# PP_8_14_2012.net
KiCad netlist of a schematic drawn in Altium Designer
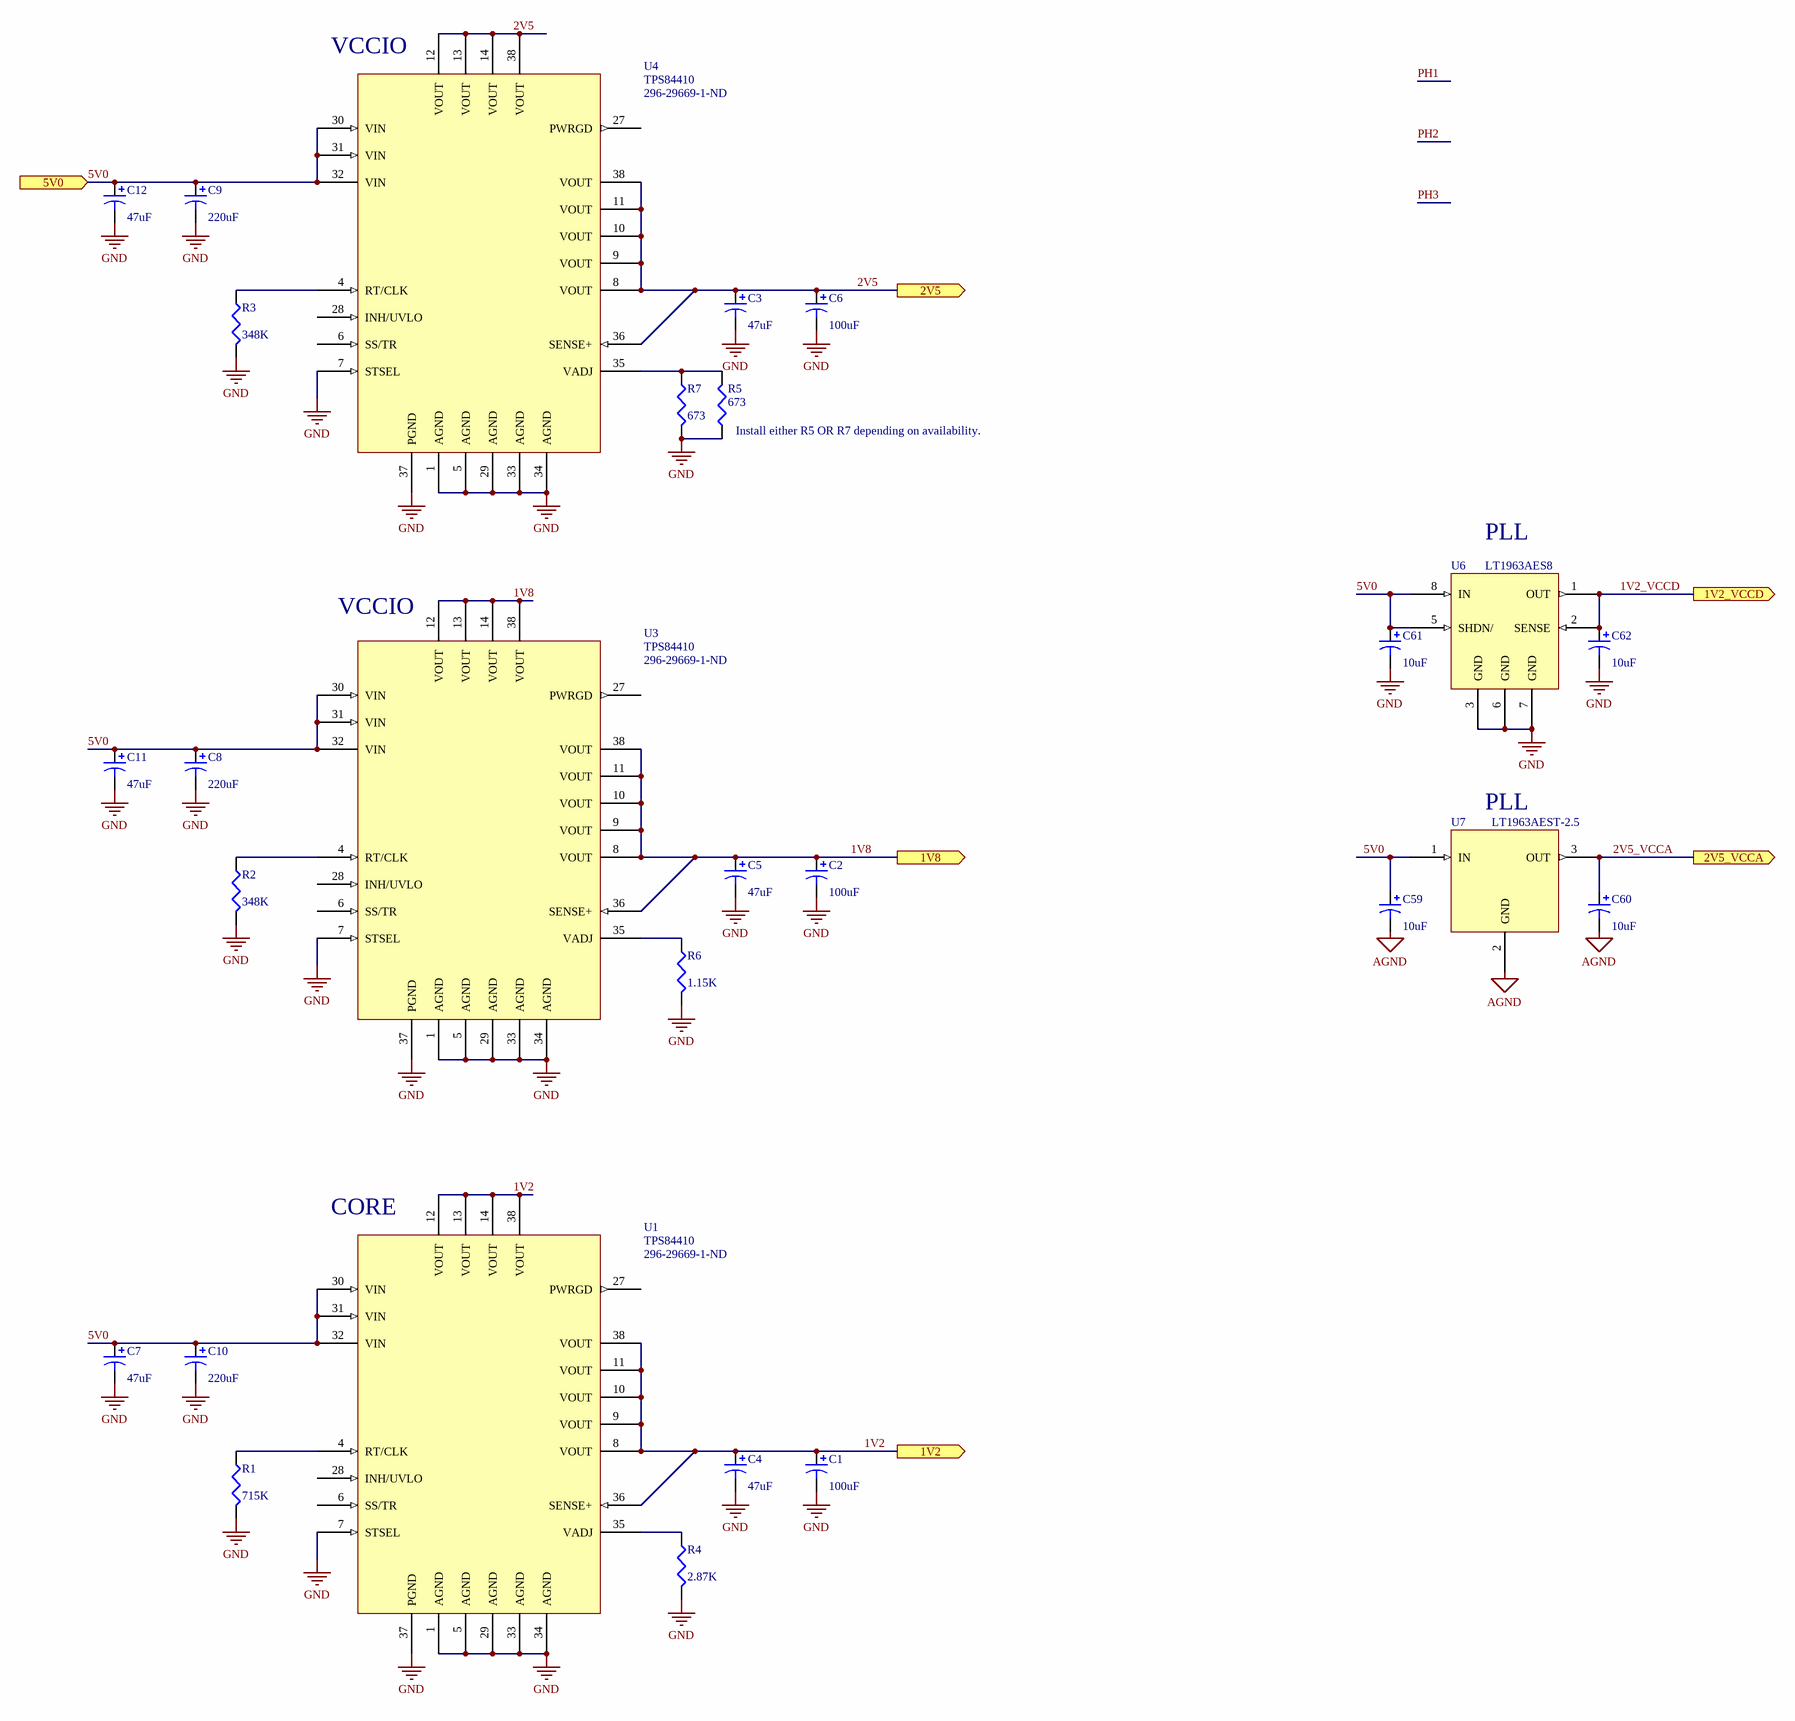
[diagram p0: PP 8_14_2012.SchDoc]

(export (version "E")
  (design (tool "Eeschema 10.0.6"))
  (components
    (comp (ref "C1")
      (value "100uF")
      (footprint "TC3528-1411")
      (description "CAP TANT 100UF 10V 20% 1210")
      (fields (field (name "Comment") "100 uF") (field (name "PUBLISHER") "Altium Limited"))
      (libsource (lib "Miscellaneous Devices") (part "Cap Pol3"))
    )
    (comp (ref "C2")
      (value "100uF")
      (footprint "TC3528-1411")
      (description "CAP TANT 100UF 10V 20% 1210")
      (fields (field (name "Comment") "100 uF") (field (name "PUBLISHER") "Altium Limited"))
      (libsource (lib "Miscellaneous Devices") (part "Cap Pol3"))
    )
    (comp (ref "C3")
      (value "47uF")
      (footprint "TC3528-1411")
      (description "CAP TANT 47UF 10V 10% 1411")
      (fields (field (name "Comment") "100 uF") (field (name "PUBLISHER") "Altium Limited"))
      (libsource (lib "Miscellaneous Devices") (part "Cap Pol3"))
    )
    (comp (ref "C4")
      (value "47uF")
      (footprint "TC3528-1411")
      (description "CAP TANT 47UF 10V 10% 1411")
      (fields (field (name "Comment") "47 uF") (field (name "PUBLISHER") "Altium Limited"))
      (libsource (lib "Miscellaneous Devices") (part "Cap Pol3"))
    )
    (comp (ref "C5")
      (value "47uF")
      (footprint "TC3528-1411")
      (description "CAP TANT 47UF 10V 10% 1411")
      (fields (field (name "Comment") "47 uF") (field (name "PUBLISHER") "Altium Limited"))
      (libsource (lib "Miscellaneous Devices") (part "Cap Pol3"))
    )
    (comp (ref "C6")
      (value "100uF")
      (footprint "TC3528-1411")
      (description "CAP TANT 100UF 10V 20% 1210")
      (fields (field (name "Comment") "47 uF") (field (name "PUBLISHER") "Altium Limited"))
      (libsource (lib "Miscellaneous Devices") (part "Cap Pol3"))
    )
    (comp (ref "C7")
      (value "47uF")
      (footprint "TC3528-1411")
      (description "CAP TANT 47UF 10V 10% 1411")
      (fields (field (name "Comment") "220uF") (field (name "PUBLISHER") "Altium Limited"))
      (libsource (lib "Miscellaneous Devices") (part "Cap Pol3"))
    )
    (comp (ref "C8")
      (value "220uF")
      (footprint "TC3528-1411")
      (description "CAP TANT 220UF 10V 20% 1210")
      (fields (field (name "PUBLISHER") "Altium Limited"))
      (libsource (lib "Miscellaneous Devices") (part "Cap Pol3"))
    )
    (comp (ref "C9")
      (value "220uF")
      (footprint "TC3528-1411")
      (description "CAP TANT 220UF 10V 20% 1210")
      (fields (field (name "PUBLISHER") "Altium Limited"))
      (libsource (lib "Miscellaneous Devices") (part "Cap Pol3"))
    )
    (comp (ref "C10")
      (value "220uF")
      (footprint "TC3528-1411")
      (description "CAP TANT 220UF 10V 20% 1210")
      (fields (field (name "Comment") "47uF") (field (name "PUBLISHER") "Altium Limited"))
      (libsource (lib "Miscellaneous Devices") (part "Cap Pol3"))
    )
    (comp (ref "C11")
      (value "47uF")
      (footprint "TC3528-1411")
      (description "CAP TANT 47UF 10V 10% 1411")
      (fields (field (name "Comment") "47 uF") (field (name "PUBLISHER") "Altium Limited"))
      (libsource (lib "Miscellaneous Devices") (part "Cap Pol3"))
    )
    (comp (ref "C12")
      (value "47uF")
      (footprint "TC3528-1411")
      (description "CAP TANT 47UF 10V 10% 1411")
      (fields (field (name "Comment") "47 uF") (field (name "PUBLISHER") "Altium Limited"))
      (libsource (lib "Miscellaneous Devices") (part "Cap Pol3"))
    )
    (comp (ref "C59")
      (value "10uF")
      (footprint "1206")
      (description "CAP TANT 10UF 16V 20% 1206")
      (fields (field (name "PUBLISHER") "Altium Limited"))
      (libsource (lib "Miscellaneous Devices") (part "Cap Pol3"))
    )
    (comp (ref "C60")
      (value "10uF")
      (footprint "1206")
      (description "CAP TANT 10UF 16V 20% 1206")
      (fields (field (name "PUBLISHER") "Altium Limited"))
      (libsource (lib "Miscellaneous Devices") (part "Cap Pol3"))
    )
    (comp (ref "C61")
      (value "10uF")
      (footprint "1206")
      (description "CAP TANT 10UF 16V 20% 1206")
      (fields (field (name "PUBLISHER") "Altium Limited"))
      (libsource (lib "Miscellaneous Devices") (part "Cap Pol3"))
    )
    (comp (ref "C62")
      (value "10uF")
      (footprint "1206")
      (description "CAP TANT 10UF 16V 20% 1206")
      (fields (field (name "PUBLISHER") "Altium Limited"))
      (libsource (lib "Miscellaneous Devices") (part "Cap Pol3"))
    )
    (comp (ref "R1")
      (value "715K")
      (footprint "J1-0603")
      (description "RES 2.87K OHM 1/10W 1% 0603 SMD")
      (fields (field (name "PUBLISHER") "Altium Limited"))
      (libsource (lib "Miscellaneous Devices") (part "Res3"))
    )
    (comp (ref "R2")
      (value "348K")
      (footprint "J1-0603")
      (description "RES 348K OHM 1/10W 1% 0603 SMD")
      (fields (field (name "PUBLISHER") "Altium Limited"))
      (libsource (lib "Miscellaneous Devices") (part "Res3"))
    )
    (comp (ref "R3")
      (value "348K")
      (footprint "J1-0603")
      (description "RES 348K OHM 1/10W 1% 0603 SMD")
      (fields (field (name "PUBLISHER") "Altium Limited"))
      (libsource (lib "Miscellaneous Devices") (part "Res3"))
    )
    (comp (ref "R4")
      (value "2.87K")
      (footprint "J1-0603")
      (description "RES 2.87K OHM 1/10W 1% 0603 SMD")
      (fields (field (name "PUBLISHER") "Altium Limited"))
      (libsource (lib "Miscellaneous Devices") (part "Res3"))
    )
    (comp (ref "R5")
      (value "673")
      (footprint "RES 0.3 x 0.025")
      (description "Metal Film Resistors - Through Hole 1/8watt 673ohms .1% 10ppm")
      (fields (field (name "PUBLISHER") "Altium Limited"))
      (libsource (lib "Miscellaneous Devices") (part "Res3"))
    )
    (comp (ref "R6")
      (value "1.15K")
      (footprint "J1-0603")
      (description "RES 1.15K OHM 1/10W 1% 0603 SMD")
      (fields (field (name "PUBLISHER") "Altium Limited"))
      (libsource (lib "Miscellaneous Devices") (part "Res3"))
    )
    (comp (ref "R7")
      (value "673")
      (footprint "J1-0603")
      (description "Metal Film Resistors - Through Hole 1/8watt 673ohms .1% 10ppm")
      (fields (field (name "PUBLISHER") "Altium Limited"))
      (libsource (lib "Miscellaneous Devices") (part "Res3"))
    )
    (comp (ref "U1")
      (value "TPS84410")
      (footprint "QFN-N39")
      (fields (field (name "SUPPLIER PART NUMBER 1") "296-29669-1-ND"))
      (libsource (lib "FLS Data Formatter") (part "TPS84410"))
    )
    (comp (ref "U3")
      (value "TPS84410")
      (footprint "QFN-N39")
      (fields (field (name "SUPPLIER PART NUMBER 1") "296-29669-1-ND"))
      (libsource (lib "FLS Data Formatter") (part "TPS84410"))
    )
    (comp (ref "U4")
      (value "TPS84410")
      (footprint "QFN-N39")
      (fields (field (name "SUPPLIER PART NUMBER 1") "296-29669-1-ND"))
      (libsource (lib "FLS Data Formatter") (part "TPS84410"))
    )
    (comp (ref "U6") (value "LT1963AES8") (footprint "SO8_L") (libsource (lib "alanb2") (part "LT1963A")))
    (comp (ref "U7")
      (value "LT1963AEST-2.5")
      (footprint "SOT-223 LT1963A")
      (libsource (lib "alanb2") (part "LT1963AEST-2.5"))
    )
  )
  (nets
    (net (code "1") (name "/1V2") (class "Default")
      (node (ref "C1") (pin "1") (pinfunction "1_1") (pintype "passive"))
      (node (ref "C4") (pin "1") (pinfunction "1_1") (pintype "passive"))
      (node (ref "U1") (pin "10") (pinfunction "VOUT_10") (pintype "power_in"))
      (node (ref "U1") (pin "11") (pinfunction "VOUT_11") (pintype "power_in"))
      (node (ref "U1") (pin "12") (pinfunction "VOUT_12") (pintype "power_in"))
      (node (ref "U1") (pin "13") (pinfunction "VOUT_13") (pintype "power_in"))
      (node (ref "U1") (pin "14") (pinfunction "VOUT_14") (pintype "power_in"))
      (node (ref "U1") (pin "36") (pinfunction "SENSE+_36") (pintype "input"))
      (node (ref "U1") (pin "38") (pinfunction "VOUT_38") (pintype "power_in"))
      (node (ref "U1") (pin "8") (pinfunction "VOUT_8") (pintype "power_in"))
      (node (ref "U1") (pin "9") (pinfunction "VOUT_9") (pintype "power_in"))
    )
    (net (code "2") (name "/1V2_VCCD") (class "Default")
      (node (ref "C62") (pin "1") (pinfunction "1_1") (pintype "passive"))
      (node (ref "U6") (pin "1") (pinfunction "OUT_1") (pintype "output"))
      (node (ref "U6") (pin "2") (pinfunction "SENSE_2") (pintype "input"))
    )
    (net (code "3") (name "/1V8") (class "Default")
      (node (ref "C2") (pin "1") (pinfunction "1_1") (pintype "passive"))
      (node (ref "C5") (pin "1") (pinfunction "1_1") (pintype "passive"))
      (node (ref "U3") (pin "10") (pinfunction "VOUT_10") (pintype "power_in"))
      (node (ref "U3") (pin "11") (pinfunction "VOUT_11") (pintype "power_in"))
      (node (ref "U3") (pin "12") (pinfunction "VOUT_12") (pintype "power_in"))
      (node (ref "U3") (pin "13") (pinfunction "VOUT_13") (pintype "power_in"))
      (node (ref "U3") (pin "14") (pinfunction "VOUT_14") (pintype "power_in"))
      (node (ref "U3") (pin "36") (pinfunction "SENSE+_36") (pintype "input"))
      (node (ref "U3") (pin "38") (pinfunction "VOUT_38") (pintype "power_in"))
      (node (ref "U3") (pin "8") (pinfunction "VOUT_8") (pintype "power_in"))
      (node (ref "U3") (pin "9") (pinfunction "VOUT_9") (pintype "power_in"))
    )
    (net (code "4") (name "/2V5") (class "Default")
      (node (ref "C3") (pin "1") (pinfunction "1_1") (pintype "passive"))
      (node (ref "C6") (pin "1") (pinfunction "1_1") (pintype "passive"))
      (node (ref "U4") (pin "10") (pinfunction "VOUT_10") (pintype "power_in"))
      (node (ref "U4") (pin "11") (pinfunction "VOUT_11") (pintype "power_in"))
      (node (ref "U4") (pin "12") (pinfunction "VOUT_12") (pintype "power_in"))
      (node (ref "U4") (pin "13") (pinfunction "VOUT_13") (pintype "power_in"))
      (node (ref "U4") (pin "14") (pinfunction "VOUT_14") (pintype "power_in"))
      (node (ref "U4") (pin "36") (pinfunction "SENSE+_36") (pintype "input"))
      (node (ref "U4") (pin "38") (pinfunction "VOUT_38") (pintype "power_in"))
      (node (ref "U4") (pin "8") (pinfunction "VOUT_8") (pintype "power_in"))
      (node (ref "U4") (pin "9") (pinfunction "VOUT_9") (pintype "power_in"))
    )
    (net (code "5") (name "/2V5_VCCA") (class "Default")
      (node (ref "C60") (pin "1") (pinfunction "1_1") (pintype "passive"))
      (node (ref "U7") (pin "3") (pinfunction "OUT_3") (pintype "output"))
    )
    (net (code "6") (name "/5V0") (class "Default")
      (node (ref "C10") (pin "1") (pinfunction "1_1") (pintype "passive"))
      (node (ref "C11") (pin "1") (pinfunction "1_1") (pintype "passive"))
      (node (ref "C12") (pin "1") (pinfunction "1_1") (pintype "passive"))
      (node (ref "C59") (pin "1") (pinfunction "1_1") (pintype "passive"))
      (node (ref "C61") (pin "1") (pinfunction "1_1") (pintype "passive"))
      (node (ref "C7") (pin "1") (pinfunction "1_1") (pintype "passive"))
      (node (ref "C8") (pin "1") (pinfunction "1_1") (pintype "passive"))
      (node (ref "C9") (pin "1") (pinfunction "1_1") (pintype "passive"))
      (node (ref "U1") (pin "30") (pinfunction "VIN_30") (pintype "input"))
      (node (ref "U1") (pin "31") (pinfunction "VIN_31") (pintype "input"))
      (node (ref "U1") (pin "32") (pinfunction "VIN_32") (pintype "power_in"))
      (node (ref "U3") (pin "30") (pinfunction "VIN_30") (pintype "input"))
      (node (ref "U3") (pin "31") (pinfunction "VIN_31") (pintype "input"))
      (node (ref "U3") (pin "32") (pinfunction "VIN_32") (pintype "power_in"))
      (node (ref "U4") (pin "30") (pinfunction "VIN_30") (pintype "input"))
      (node (ref "U4") (pin "31") (pinfunction "VIN_31") (pintype "input"))
      (node (ref "U4") (pin "32") (pinfunction "VIN_32") (pintype "power_in"))
      (node (ref "U6") (pin "5") (pinfunction "SHDN/_5") (pintype "input"))
      (node (ref "U6") (pin "8") (pinfunction "IN_8") (pintype "input"))
      (node (ref "U7") (pin "1") (pinfunction "IN_1") (pintype "input"))
    )
    (net (code "10") (name "AGND") (class "Default")
      (node (ref "C59") (pin "2") (pinfunction "2_2") (pintype "passive"))
      (node (ref "C60") (pin "2") (pinfunction "2_2") (pintype "passive"))
      (node (ref "U7") (pin "2") (pinfunction "GND_2") (pintype "power_in"))
    )
    (net (code "11") (name "GND") (class "Default")
      (node (ref "C1") (pin "2") (pinfunction "2_2") (pintype "passive"))
      (node (ref "C10") (pin "2") (pinfunction "2_2") (pintype "passive"))
      (node (ref "C11") (pin "2") (pinfunction "2_2") (pintype "passive"))
      (node (ref "C12") (pin "2") (pinfunction "2_2") (pintype "passive"))
      (node (ref "C2") (pin "2") (pinfunction "2_2") (pintype "passive"))
      (node (ref "C3") (pin "2") (pinfunction "2_2") (pintype "passive"))
      (node (ref "C4") (pin "2") (pinfunction "2_2") (pintype "passive"))
      (node (ref "C5") (pin "2") (pinfunction "2_2") (pintype "passive"))
      (node (ref "C6") (pin "2") (pinfunction "2_2") (pintype "passive"))
      (node (ref "C61") (pin "2") (pinfunction "2_2") (pintype "passive"))
      (node (ref "C62") (pin "2") (pinfunction "2_2") (pintype "passive"))
      (node (ref "C7") (pin "2") (pinfunction "2_2") (pintype "passive"))
      (node (ref "C8") (pin "2") (pinfunction "2_2") (pintype "passive"))
      (node (ref "C9") (pin "2") (pinfunction "2_2") (pintype "passive"))
      (node (ref "R1") (pin "2") (pinfunction "2_2") (pintype "passive"))
      (node (ref "R2") (pin "2") (pinfunction "2_2") (pintype "passive"))
      (node (ref "R3") (pin "2") (pinfunction "2_2") (pintype "passive"))
      (node (ref "R4") (pin "2") (pinfunction "2_2") (pintype "passive"))
      (node (ref "R5") (pin "1") (pinfunction "1_1") (pintype "passive"))
      (node (ref "R6") (pin "2") (pinfunction "2_2") (pintype "passive"))
      (node (ref "R7") (pin "2") (pinfunction "2_2") (pintype "passive"))
      (node (ref "U1") (pin "1") (pinfunction "AGND_1") (pintype "power_in"))
      (node (ref "U1") (pin "29") (pinfunction "AGND_29") (pintype "power_in"))
      (node (ref "U1") (pin "33") (pinfunction "AGND_33") (pintype "power_in"))
      (node (ref "U1") (pin "34") (pinfunction "AGND_34") (pintype "power_in"))
      (node (ref "U1") (pin "37") (pinfunction "PGND_37") (pintype "power_in"))
      (node (ref "U1") (pin "5") (pinfunction "AGND_5") (pintype "power_in"))
      (node (ref "U1") (pin "7") (pinfunction "STSEL_7") (pintype "input"))
      (node (ref "U3") (pin "1") (pinfunction "AGND_1") (pintype "power_in"))
      (node (ref "U3") (pin "29") (pinfunction "AGND_29") (pintype "power_in"))
      (node (ref "U3") (pin "33") (pinfunction "AGND_33") (pintype "power_in"))
      (node (ref "U3") (pin "34") (pinfunction "AGND_34") (pintype "power_in"))
      (node (ref "U3") (pin "37") (pinfunction "PGND_37") (pintype "power_in"))
      (node (ref "U3") (pin "5") (pinfunction "AGND_5") (pintype "power_in"))
      (node (ref "U3") (pin "7") (pinfunction "STSEL_7") (pintype "input"))
      (node (ref "U4") (pin "1") (pinfunction "AGND_1") (pintype "power_in"))
      (node (ref "U4") (pin "29") (pinfunction "AGND_29") (pintype "power_in"))
      (node (ref "U4") (pin "33") (pinfunction "AGND_33") (pintype "power_in"))
      (node (ref "U4") (pin "34") (pinfunction "AGND_34") (pintype "power_in"))
      (node (ref "U4") (pin "37") (pinfunction "PGND_37") (pintype "power_in"))
      (node (ref "U4") (pin "5") (pinfunction "AGND_5") (pintype "power_in"))
      (node (ref "U4") (pin "7") (pinfunction "STSEL_7") (pintype "input"))
      (node (ref "U6") (pin "3") (pinfunction "GND_3") (pintype "power_in"))
      (node (ref "U6") (pin "6") (pinfunction "GND_6") (pintype "power_in"))
      (node (ref "U6") (pin "7") (pinfunction "GND_7") (pintype "power_in"))
    )
    (net (code "12") (name "Net-(U1-RT{slash}CLK)") (class "Default")
      (node (ref "R1") (pin "1") (pinfunction "1_1") (pintype "passive"))
      (node (ref "U1") (pin "4") (pinfunction "RT/CLK_4") (pintype "input"))
    )
    (net (code "13") (name "Net-(U1-VADJ)") (class "Default")
      (node (ref "R4") (pin "1") (pinfunction "1_1") (pintype "passive"))
      (node (ref "U1") (pin "35") (pinfunction "VADJ_35") (pintype "passive"))
    )
    (net (code "14") (name "Net-(U3-RT{slash}CLK)") (class "Default")
      (node (ref "R2") (pin "1") (pinfunction "1_1") (pintype "passive"))
      (node (ref "U3") (pin "4") (pinfunction "RT/CLK_4") (pintype "input"))
    )
    (net (code "15") (name "Net-(U3-VADJ)") (class "Default")
      (node (ref "R6") (pin "1") (pinfunction "1_1") (pintype "passive"))
      (node (ref "U3") (pin "35") (pinfunction "VADJ_35") (pintype "passive"))
    )
    (net (code "16") (name "Net-(U4-RT{slash}CLK)") (class "Default")
      (node (ref "R3") (pin "1") (pinfunction "1_1") (pintype "passive"))
      (node (ref "U4") (pin "4") (pinfunction "RT/CLK_4") (pintype "input"))
    )
    (net (code "17") (name "Net-(U4-VADJ)") (class "Default")
      (node (ref "R5") (pin "2") (pinfunction "2_2") (pintype "passive"))
      (node (ref "R7") (pin "1") (pinfunction "1_1") (pintype "passive"))
      (node (ref "U4") (pin "35") (pinfunction "VADJ_35") (pintype "passive"))
    )
    (net (code "18") (name "unconnected-(U1-INH{slash}UVLO-Pad28)") (class "Default")
      (node (ref "U1") (pin "28") (pinfunction "INH/UVLO_28") (pintype "input"))
    )
    (net (code "19") (name "unconnected-(U1-PWRGD-Pad27)") (class "Default")
      (node (ref "U1") (pin "27") (pinfunction "PWRGD_27") (pintype "output"))
    )
    (net (code "20") (name "unconnected-(U1-SS{slash}TR-Pad6)") (class "Default")
      (node (ref "U1") (pin "6") (pinfunction "SS/TR_6") (pintype "input"))
    )
    (net (code "21") (name "unconnected-(U3-INH{slash}UVLO-Pad28)") (class "Default")
      (node (ref "U3") (pin "28") (pinfunction "INH/UVLO_28") (pintype "input"))
    )
    (net (code "22") (name "unconnected-(U3-PWRGD-Pad27)") (class "Default")
      (node (ref "U3") (pin "27") (pinfunction "PWRGD_27") (pintype "output"))
    )
    (net (code "23") (name "unconnected-(U3-SS{slash}TR-Pad6)") (class "Default")
      (node (ref "U3") (pin "6") (pinfunction "SS/TR_6") (pintype "input"))
    )
    (net (code "24") (name "unconnected-(U4-INH{slash}UVLO-Pad28)") (class "Default")
      (node (ref "U4") (pin "28") (pinfunction "INH/UVLO_28") (pintype "input"))
    )
    (net (code "25") (name "unconnected-(U4-PWRGD-Pad27)") (class "Default")
      (node (ref "U4") (pin "27") (pinfunction "PWRGD_27") (pintype "output"))
    )
    (net (code "26") (name "unconnected-(U4-SS{slash}TR-Pad6)") (class "Default")
      (node (ref "U4") (pin "6") (pinfunction "SS/TR_6") (pintype "input"))
    )
    (net (code "27") (name "unconnected-(U6-NC-Pad4)") (class "Default")
      (node (ref "U6") (pin "4") (pinfunction "NC_4") (pintype "passive"))
    )
  )
)
